# ledB_sch-raw.net
KiCad netlist of a schematic drawn in EAGLE
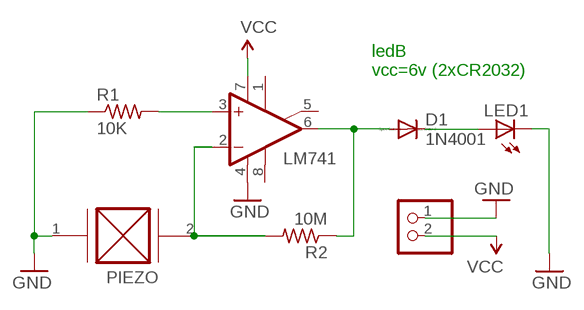
[diagram p0: schematic, sheet 1]

(export (version "E")
  (design (tool "Eeschema 10.0.6"))
  (components
    (comp (ref "D1")
      (value "1N4001")
      (footprint "eagle-import:DO-214AC")
      (libsource (lib "eagle-import") (part "DIODE-DO-214AC"))
    )
    (comp (ref "JP1")
      (value "6V+")
      (footprint "eagle-import:1X02_ROUND")
      (libsource (lib "eagle-import") (part "HEADER-1X2ROUND"))
    )
    (comp (ref "LED1")
      (value "LED1206")
      (footprint "eagle-import:LED-1206")
      (libsource (lib "eagle-import") (part "LED1206"))
    )
    (comp (ref "OPAMP")
      (value "LM741")
      (footprint "eagle-import:SO08")
      (libsource (lib "eagle-import") (part "741DLM"))
    )
    (comp (ref "PIEZO")
      (value "PIEZO")
      (footprint "eagle-import:1X02_ROUND")
      (libsource (lib "eagle-import") (part "PIEZO"))
    )
    (comp (ref "R1")
      (value "10K")
      (footprint "eagle-import:M1206")
      (libsource (lib "eagle-import") (part "R-US_M1206"))
    )
    (comp (ref "R2")
      (value "10M")
      (footprint "eagle-import:M1206")
      (libsource (lib "eagle-import") (part "R-US_M1206"))
    )
  )
  (nets
    (net (code "1") (name "GND") (class "Default")
      (node (ref "JP1") (pin "1") (pinfunction "1_1") (pintype "passive"))
      (node (ref "LED1") (pin "C") (pinfunction "C_C") (pintype "passive"))
      (node (ref "OPAMP") (pin "4") (pinfunction "V-_4") (pintype "power_in"))
      (node (ref "PIEZO") (pin "1") (pinfunction "GND_1") (pintype "passive"))
      (node (ref "R1") (pin "1") (pinfunction "1_1") (pintype "passive"))
    )
    (net (code "2") (name "Net-(D1-PadC)") (class "Default")
      (node (ref "D1") (pin "C") (pinfunction "C_C") (pintype "passive"))
      (node (ref "LED1") (pin "A") (pinfunction "A_A") (pintype "passive"))
    )
    (net (code "3") (name "Net-(OPAMP-+IN)") (class "Default")
      (node (ref "OPAMP") (pin "3") (pinfunction "+IN_3") (pintype "input"))
      (node (ref "R1") (pin "2") (pinfunction "2_2") (pintype "passive"))
    )
    (net (code "4") (name "Net-(OPAMP--IN)") (class "Default")
      (node (ref "OPAMP") (pin "2") (pinfunction "-IN_2") (pintype "input"))
      (node (ref "PIEZO") (pin "2") (pinfunction "OUT+_2") (pintype "passive"))
      (node (ref "R2") (pin "2") (pinfunction "2_2") (pintype "passive"))
    )
    (net (code "5") (name "Net-(OPAMP-OUT)") (class "Default")
      (node (ref "D1") (pin "A") (pinfunction "A_A") (pintype "passive"))
      (node (ref "OPAMP") (pin "6") (pinfunction "OUT_6") (pintype "output"))
      (node (ref "R2") (pin "1") (pinfunction "1_1") (pintype "passive"))
    )
    (net (code "6") (name "VCC") (class "Default")
      (node (ref "JP1") (pin "2") (pinfunction "2_2") (pintype "passive"))
      (node (ref "OPAMP") (pin "7") (pinfunction "V+_7") (pintype "power_in"))
    )
    (net (code "7") (name "unconnected-(OPAMP-ON1-Pad1)") (class "Default")
      (node (ref "OPAMP") (pin "1") (pinfunction "ON1_1") (pintype "passive"))
    )
    (net (code "8") (name "unconnected-(OPAMP-ON2-Pad5)") (class "Default")
      (node (ref "OPAMP") (pin "5") (pinfunction "ON2_5") (pintype "passive"))
    )
    (net (code "9") (name "unconnected-(OPAMP-OPT-Pad8)") (class "Default")
      (node (ref "OPAMP") (pin "8") (pinfunction "OPT_8") (pintype "passive"))
    )
  )
)
